# Sheet1.net
KiCad netlist of a schematic drawn in Altium Designer
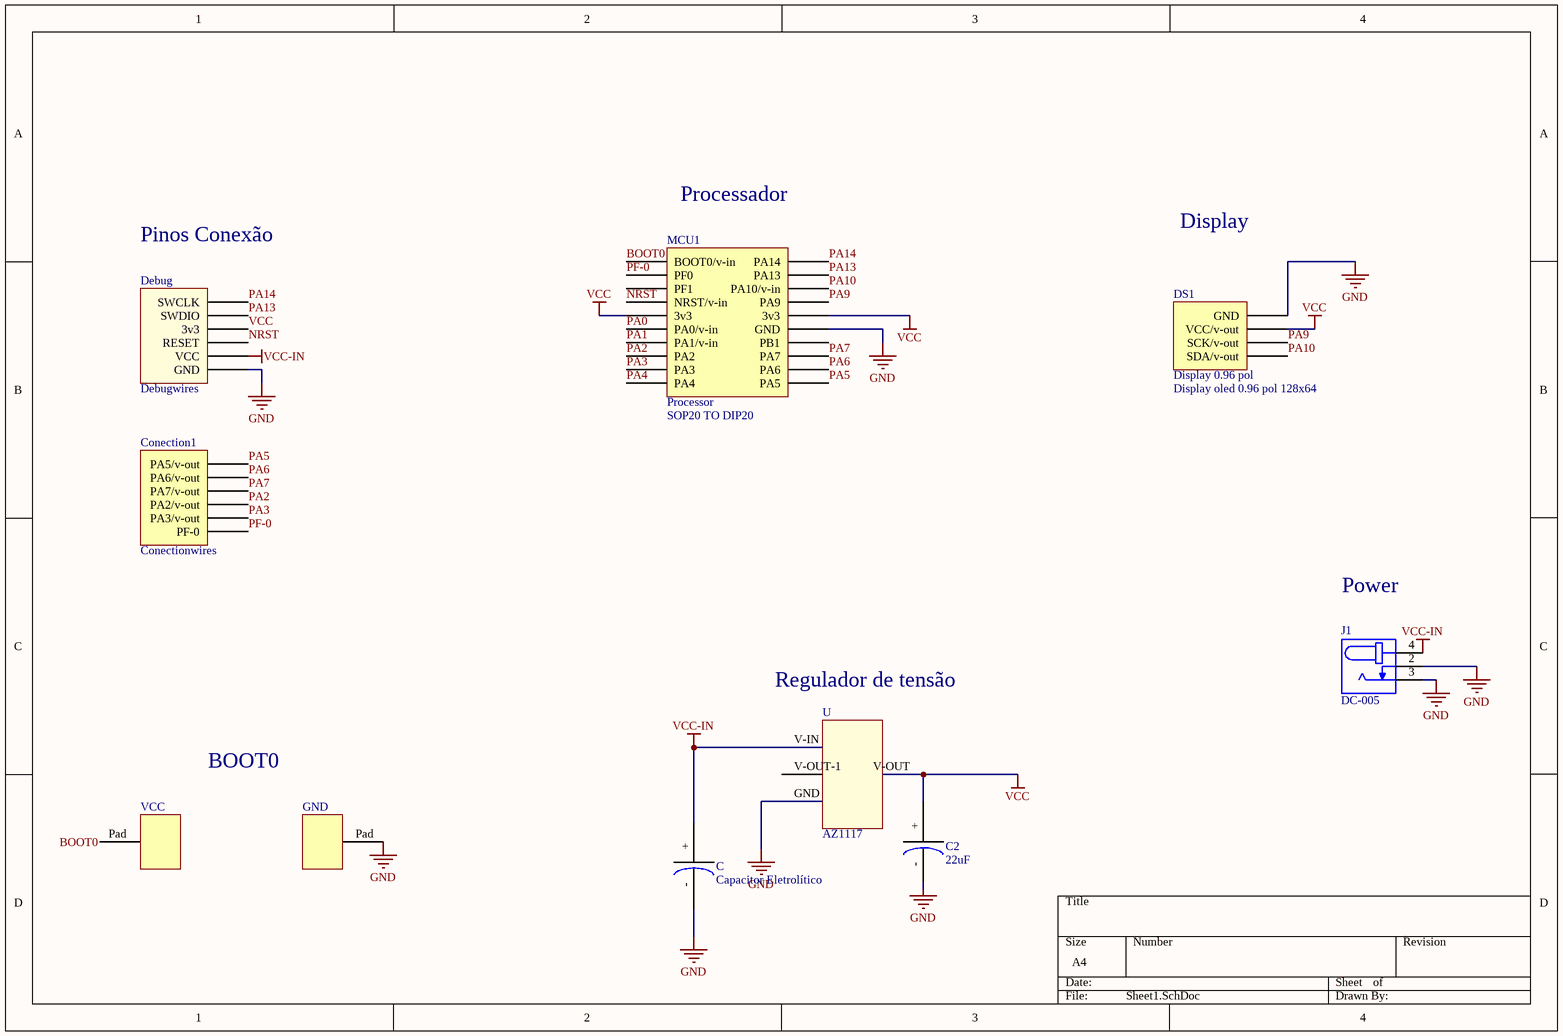
[diagram p0: Sheet1.SchDoc]

(export (version "E")
  (design (tool "Eeschema 10.0.6"))
  (components
    (comp (ref "C")
      (value "Capacitor Eletrolítico")
      (footprint "Capacitor")
      (libsource (lib "") (part "Capacitor Eletrolítico_1"))
    )
    (comp (ref "C2")
      (value "22uF")
      (footprint "Capacitor")
      (libsource (lib "Schlib1") (part "Capacitor Eletrolítico"))
    )
    (comp (ref "Conection1")
      (value "Conectionwires")
      (footprint "Conectionwires")
      (description "6 out")
      (libsource (lib "Schlib1") (part "Conectionwires"))
    )
    (comp (ref "Debug")
      (value "Debugwires")
      (footprint "Debugwires")
      (description "2 in")
      (libsource (lib "Schlib1") (part "Debugwires"))
    )
    (comp (ref "DS1")
      (value "Display 0.96 pol")
      (footprint "Display oled")
      (description "0.96 pol 24.7x27 cm")
      (fields (field (name "INFORMATIONS") "Display oled 0.96 pol 128x64"))
      (libsource (lib "Schlib1") (part "Display oled"))
    )
    (comp (ref "GND") (value "Pad") (footprint "Pad") (libsource (lib "Schlib1") (part "Pad")))
    (comp (ref "J1")
      (value "DC-005")
      (footprint "NINIGI_DC-005")
      (description "Polymeric PTC Resettable Fuse 15V 50mA Ih Surface Mount 0603 _1608 Metric_, Concave")
      (fields (field (name "MF") "Littelfuse Inc."))
      (libsource (lib "Schlib1") (part "DC-005"))
    )
    (comp (ref "MCU1")
      (value "Processor")
      (footprint "Processor")
      (description "Processor arm Stm32f0xx")
      (fields (field (name "ADAPTER") "SOP20 TO DIP20"))
      (libsource (lib "Schlib1") (part "Processor"))
    )
    (comp (ref "U")
      (value "AZ1117")
      (footprint "AZ1117")
      (description "Converter 5v to 3.3v")
      (libsource (lib "Schlib1") (part "AZ1117"))
    )
    (comp (ref "VCC") (value "Pad") (footprint "Pad") (libsource (lib "") (part "Pad_1")))
  )
  (nets
    (net (code "1") (name "/BOOT0") (class "Default")
      (node (ref "MCU1") (pin "BOOT0") (pinfunction "BOOT0/v-in_BOOT0") (pintype "passive"))
      (node (ref "VCC") (pin "Pad") (pinfunction "Pad_Pad") (pintype "passive"))
    )
    (net (code "2") (name "/NRST") (class "Default")
      (node (ref "Debug") (pin "RESET") (pinfunction "RESET_RESET") (pintype "passive"))
      (node (ref "MCU1") (pin "NRST") (pinfunction "NRST/v-in_NRST") (pintype "passive"))
    )
    (net (code "3") (name "/PA0") (class "Default")
      (node (ref "MCU1") (pin "PA0") (pinfunction "PA0/v-in_PA0") (pintype "passive"))
    )
    (net (code "4") (name "/PA1") (class "Default")
      (node (ref "MCU1") (pin "PA1") (pinfunction "PA1/v-in_PA1") (pintype "passive"))
    )
    (net (code "5") (name "/PA2") (class "Default")
      (node (ref "Conection1") (pin "PA2") (pinfunction "PA2/v-out_PA2") (pintype "passive"))
      (node (ref "MCU1") (pin "PA2") (pinfunction "PA2_PA2") (pintype "passive"))
    )
    (net (code "6") (name "/PA3") (class "Default")
      (node (ref "Conection1") (pin "PA3") (pinfunction "PA3/v-out_PA3") (pintype "passive"))
      (node (ref "MCU1") (pin "PA3") (pinfunction "PA3_PA3") (pintype "passive"))
    )
    (net (code "7") (name "/PA4") (class "Default")
      (node (ref "MCU1") (pin "PA4") (pinfunction "PA4_PA4") (pintype "passive"))
    )
    (net (code "8") (name "/PA5") (class "Default")
      (node (ref "Conection1") (pin "PA5") (pinfunction "PA5/v-out_PA5") (pintype "passive"))
      (node (ref "MCU1") (pin "PA5") (pinfunction "PA5_PA5") (pintype "passive"))
    )
    (net (code "9") (name "/PA6") (class "Default")
      (node (ref "Conection1") (pin "PA6") (pinfunction "PA6/v-out_PA6") (pintype "passive"))
      (node (ref "MCU1") (pin "PA6") (pinfunction "PA6_PA6") (pintype "passive"))
    )
    (net (code "10") (name "/PA7") (class "Default")
      (node (ref "Conection1") (pin "PA7") (pinfunction "PA7/v-out_PA7") (pintype "passive"))
      (node (ref "MCU1") (pin "PA7") (pinfunction "PA7_PA7") (pintype "passive"))
    )
    (net (code "11") (name "/PA9") (class "Default")
      (node (ref "DS1") (pin "SCK") (pinfunction "SCK/v-out_SCK") (pintype "passive"))
      (node (ref "MCU1") (pin "PA9") (pinfunction "PA9_PA9") (pintype "passive"))
    )
    (net (code "12") (name "/PA10") (class "Default")
      (node (ref "DS1") (pin "SDA") (pinfunction "SDA/v-out_SDA") (pintype "passive"))
      (node (ref "MCU1") (pin "PA10") (pinfunction "PA10/v-in_PA10") (pintype "passive"))
    )
    (net (code "13") (name "/PA13") (class "Default")
      (node (ref "Debug") (pin "PA13") (pinfunction "SWDIO_PA13") (pintype "passive"))
      (node (ref "MCU1") (pin "PA13") (pinfunction "PA13_PA13") (pintype "passive"))
    )
    (net (code "14") (name "/PA14") (class "Default")
      (node (ref "Debug") (pin "PA14") (pinfunction "SWCLK_PA14") (pintype "passive"))
      (node (ref "MCU1") (pin "PA14") (pinfunction "PA14_PA14") (pintype "passive"))
    )
    (net (code "15") (name "/PF-0") (class "Default")
      (node (ref "Conection1") (pin "PF-0") (pinfunction "PF-0_PF-0") (pintype "passive"))
      (node (ref "MCU1") (pin "PF0") (pinfunction "PF0_PF0") (pintype "passive"))
    )
    (net (code "16") (name "GND") (class "Default")
      (node (ref "C") (pin "-") (pinfunction "-_-") (pintype "passive"))
      (node (ref "C2") (pin "-") (pinfunction "-_-") (pintype "passive"))
      (node (ref "DS1") (pin "GND") (pinfunction "GND_GND") (pintype "passive"))
      (node (ref "Debug") (pin "GND") (pinfunction "GND_GND") (pintype "passive"))
      (node (ref "GND") (pin "Pad") (pinfunction "Pad_Pad") (pintype "passive"))
      (node (ref "J1") (pin "2") (pinfunction "4_2") (pintype "passive"))
      (node (ref "J1") (pin "3") (pinfunction "3_3") (pintype "passive"))
      (node (ref "MCU1") (pin "GND") (pinfunction "GND_GND") (pintype "passive"))
      (node (ref "U") (pin "GND") (pinfunction "GND_GND") (pintype "passive"))
    )
    (net (code "17") (name "VCC") (class "Default")
      (node (ref "C2") (pin "+") (pinfunction "+_+") (pintype "passive"))
      (node (ref "DS1") (pin "VCC") (pinfunction "VCC/v-out_VCC") (pintype "passive"))
      (node (ref "Debug") (pin "3v3") (pinfunction "3v3_3v3") (pintype "passive"))
      (node (ref "MCU1") (pin "3v3") (pinfunction "3v3_3v3") (pintype "passive"))
      (node (ref "U") (pin "V-OUT") (pinfunction "V-OUT_V-OUT") (pintype "passive"))
    )
    (net (code "18") (name "VCC-IN") (class "Default")
      (node (ref "C") (pin "+") (pinfunction "+_+") (pintype "passive"))
      (node (ref "Debug") (pin "VCC") (pinfunction "VCC_VCC") (pintype "passive"))
      (node (ref "J1") (pin "4") (pinfunction "2_4") (pintype "passive"))
      (node (ref "U") (pin "V-IN") (pinfunction "V-IN_V-IN") (pintype "passive"))
    )
    (net (code "19") (name "unconnected-(MCU1-PadPB1)") (class "Default")
      (node (ref "MCU1") (pin "PB1") (pinfunction "PB1_PB1") (pintype "passive"))
    )
    (net (code "20") (name "unconnected-(MCU1-PadPF1)") (class "Default")
      (node (ref "MCU1") (pin "PF1") (pinfunction "PF1_PF1") (pintype "passive"))
    )
    (net (code "21") (name "unconnected-(U-PadV-OUT-1)") (class "Default")
      (node (ref "U") (pin "V-OUT-1") (pinfunction "V-OUT-1_V-OUT-1") (pintype "passive"))
    )
  )
)
